# UiBoard.net
KiCad netlist of a schematic drawn in Altium Designer
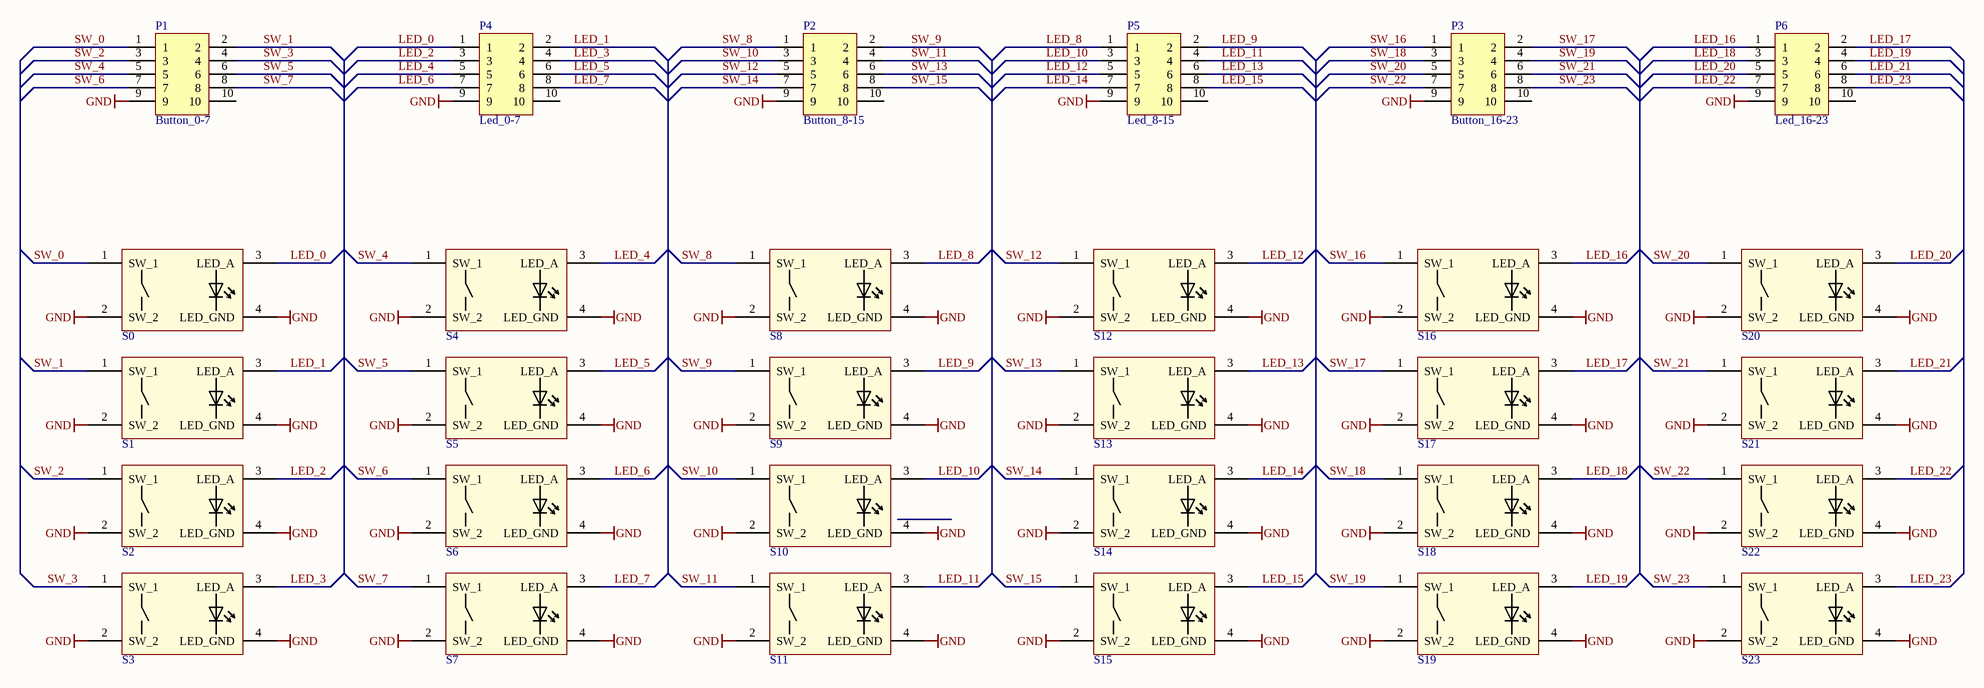
[diagram p0: UiBoard.SchDoc]

(export (version "E")
  (design (tool "Eeschema 10.0.6"))
  (components
    (comp (ref "P1")
      (value "Button_0-7")
      (footprint "10pol Header tilted:10 pol Header tilted")
      (description "10 pol Header")
      (fields (field (name "PUBLISHER") "NONLINEAR LABS"))
      (libsource (lib "10polHeader") (part "10 pol Header"))
    )
    (comp (ref "P2")
      (value "Button_8-15")
      (footprint "10pol Header tilted:10 pol Header tilted")
      (description "10 pol Header")
      (fields (field (name "PUBLISHER") "NONLINEAR LABS"))
      (libsource (lib "10polHeader") (part "10 pol Header"))
    )
    (comp (ref "P3")
      (value "Button_16-23")
      (footprint "10pol Header tilted:10 pol Header tilted")
      (description "10 pol Header")
      (fields (field (name "PUBLISHER") "NONLINEAR LABS"))
      (libsource (lib "10polHeader") (part "10 pol Header"))
    )
    (comp (ref "P4")
      (value "Led_0-7")
      (footprint "10pol Header tilted:10 pol Header tilted")
      (description "10 pol Header")
      (fields (field (name "PUBLISHER") "NONLINEAR LABS"))
      (libsource (lib "10polHeader") (part "10 pol Header"))
    )
    (comp (ref "P5")
      (value "Led_8-15")
      (footprint "10pol Header tilted:10 pol Header tilted")
      (description "10 pol Header")
      (fields (field (name "PUBLISHER") "NONLINEAR LABS"))
      (libsource (lib "10polHeader") (part "10 pol Header"))
    )
    (comp (ref "P6")
      (value "Led_16-23")
      (footprint "10pol Header tilted:10 pol Header tilted")
      (description "10 pol Header")
      (fields (field (name "PUBLISHER") "NONLINEAR LABS"))
      (libsource (lib "10polHeader") (part "10 pol Header"))
    )
    (comp (ref "S0")
      (value "Switch + LED")
      (footprint "Marquardt Taster 6425")
      (description "Marquardt Key Switch with LED - Type 6425")
      (fields (field (name "PUBLISHER") "Altium Limited"))
      (libsource (lib "SwitchLed") (part "Switch + LED"))
    )
    (comp (ref "S1")
      (value "Switch + LED")
      (footprint "Marquardt Taster 6425")
      (description "Marquardt Key Switch with LED - Type 6425")
      (fields (field (name "PUBLISHER") "Altium Limited"))
      (libsource (lib "SwitchLed") (part "Switch + LED"))
    )
    (comp (ref "S2")
      (value "Switch + LED")
      (footprint "Marquardt Taster 6425")
      (description "Marquardt Key Switch with LED - Type 6425")
      (fields (field (name "PUBLISHER") "Altium Limited"))
      (libsource (lib "SwitchLed") (part "Switch + LED"))
    )
    (comp (ref "S3")
      (value "Switch + LED")
      (footprint "Marquardt Taster 6425")
      (description "Marquardt Key Switch with LED - Type 6425")
      (fields (field (name "PUBLISHER") "Altium Limited"))
      (libsource (lib "SwitchLed") (part "Switch + LED"))
    )
    (comp (ref "S4")
      (value "Switch + LED")
      (footprint "Marquardt Taster 6425")
      (description "Marquardt Key Switch with LED - Type 6425")
      (fields (field (name "PUBLISHER") "Altium Limited"))
      (libsource (lib "SwitchLed") (part "Switch + LED"))
    )
    (comp (ref "S5")
      (value "Switch + LED")
      (footprint "Marquardt Taster 6425")
      (description "Marquardt Key Switch with LED - Type 6425")
      (fields (field (name "PUBLISHER") "Altium Limited"))
      (libsource (lib "SwitchLed") (part "Switch + LED"))
    )
    (comp (ref "S6")
      (value "Switch + LED")
      (footprint "Marquardt Taster 6425")
      (description "Marquardt Key Switch with LED - Type 6425")
      (fields (field (name "PUBLISHER") "Altium Limited"))
      (libsource (lib "SwitchLed") (part "Switch + LED"))
    )
    (comp (ref "S7")
      (value "Switch + LED")
      (footprint "Marquardt Taster 6425")
      (description "Marquardt Key Switch with LED - Type 6425")
      (fields (field (name "PUBLISHER") "Altium Limited"))
      (libsource (lib "SwitchLed") (part "Switch + LED"))
    )
    (comp (ref "S8")
      (value "Switch + LED")
      (footprint "Marquardt Taster 6425")
      (description "Marquardt Key Switch with LED - Type 6425")
      (fields (field (name "PUBLISHER") "Altium Limited"))
      (libsource (lib "SwitchLed") (part "Switch + LED"))
    )
    (comp (ref "S9")
      (value "Switch + LED")
      (footprint "Marquardt Taster 6425")
      (description "Marquardt Key Switch with LED - Type 6425")
      (fields (field (name "PUBLISHER") "Altium Limited"))
      (libsource (lib "SwitchLed") (part "Switch + LED"))
    )
    (comp (ref "S10")
      (value "Switch + LED")
      (footprint "Marquardt Taster 6425")
      (description "Marquardt Key Switch with LED - Type 6425")
      (fields (field (name "PUBLISHER") "Altium Limited"))
      (libsource (lib "SwitchLed") (part "Switch + LED"))
    )
    (comp (ref "S11")
      (value "Switch + LED")
      (footprint "Marquardt Taster 6425")
      (description "Marquardt Key Switch with LED - Type 6425")
      (fields (field (name "PUBLISHER") "Altium Limited"))
      (libsource (lib "SwitchLed") (part "Switch + LED"))
    )
    (comp (ref "S12")
      (value "Switch + LED")
      (footprint "Marquardt Taster 6425")
      (description "Marquardt Key Switch with LED - Type 6425")
      (fields (field (name "PUBLISHER") "Altium Limited"))
      (libsource (lib "SwitchLed") (part "Switch + LED"))
    )
    (comp (ref "S13")
      (value "Switch + LED")
      (footprint "Marquardt Taster 6425")
      (description "Marquardt Key Switch with LED - Type 6425")
      (fields (field (name "PUBLISHER") "Altium Limited"))
      (libsource (lib "SwitchLed") (part "Switch + LED"))
    )
    (comp (ref "S14")
      (value "Switch + LED")
      (footprint "Marquardt Taster 6425")
      (description "Marquardt Key Switch with LED - Type 6425")
      (fields (field (name "PUBLISHER") "Altium Limited"))
      (libsource (lib "SwitchLed") (part "Switch + LED"))
    )
    (comp (ref "S15")
      (value "Switch + LED")
      (footprint "Marquardt Taster 6425")
      (description "Marquardt Key Switch with LED - Type 6425")
      (fields (field (name "PUBLISHER") "Altium Limited"))
      (libsource (lib "SwitchLed") (part "Switch + LED"))
    )
    (comp (ref "S16")
      (value "Switch + LED")
      (footprint "Marquardt Taster 6425")
      (description "Marquardt Key Switch with LED - Type 6425")
      (fields (field (name "PUBLISHER") "Altium Limited"))
      (libsource (lib "SwitchLed") (part "Switch + LED"))
    )
    (comp (ref "S17")
      (value "Switch + LED")
      (footprint "Marquardt Taster 6425")
      (description "Marquardt Key Switch with LED - Type 6425")
      (fields (field (name "PUBLISHER") "Altium Limited"))
      (libsource (lib "SwitchLed") (part "Switch + LED"))
    )
    (comp (ref "S18")
      (value "Switch + LED")
      (footprint "Marquardt Taster 6425")
      (description "Marquardt Key Switch with LED - Type 6425")
      (fields (field (name "PUBLISHER") "Altium Limited"))
      (libsource (lib "SwitchLed") (part "Switch + LED"))
    )
    (comp (ref "S19")
      (value "Switch + LED")
      (footprint "Marquardt Taster 6425")
      (description "Marquardt Key Switch with LED - Type 6425")
      (fields (field (name "PUBLISHER") "Altium Limited"))
      (libsource (lib "SwitchLed") (part "Switch + LED"))
    )
    (comp (ref "S20")
      (value "Switch + LED")
      (footprint "Marquardt Taster 6425")
      (description "Marquardt Key Switch with LED - Type 6425")
      (fields (field (name "PUBLISHER") "Altium Limited"))
      (libsource (lib "SwitchLed") (part "Switch + LED"))
    )
    (comp (ref "S21")
      (value "Switch + LED")
      (footprint "Marquardt Taster 6425")
      (description "Marquardt Key Switch with LED - Type 6425")
      (fields (field (name "PUBLISHER") "Altium Limited"))
      (libsource (lib "SwitchLed") (part "Switch + LED"))
    )
    (comp (ref "S22")
      (value "Switch + LED")
      (footprint "Marquardt Taster 6425")
      (description "Marquardt Key Switch with LED - Type 6425")
      (fields (field (name "PUBLISHER") "Altium Limited"))
      (libsource (lib "SwitchLed") (part "Switch + LED"))
    )
    (comp (ref "S23")
      (value "Switch + LED")
      (footprint "Marquardt Taster 6425")
      (description "Marquardt Key Switch with LED - Type 6425")
      (fields (field (name "PUBLISHER") "Altium Limited"))
      (libsource (lib "SwitchLed") (part "Switch + LED"))
    )
  )
  (nets
    (net (code "1") (name "/LED_0") (class "Default")
      (node (ref "P4") (pin "1") (pinfunction "1_1") (pintype "passive"))
      (node (ref "S0") (pin "3") (pinfunction "LED_A_3") (pintype "passive"))
    )
    (net (code "2") (name "/LED_1") (class "Default")
      (node (ref "P4") (pin "2") (pinfunction "2_2") (pintype "passive"))
      (node (ref "S1") (pin "3") (pinfunction "LED_A_3") (pintype "passive"))
    )
    (net (code "3") (name "/LED_2") (class "Default")
      (node (ref "P4") (pin "3") (pinfunction "3_3") (pintype "passive"))
      (node (ref "S2") (pin "3") (pinfunction "LED_A_3") (pintype "passive"))
    )
    (net (code "4") (name "/LED_3") (class "Default")
      (node (ref "P4") (pin "4") (pinfunction "4_4") (pintype "passive"))
      (node (ref "S3") (pin "3") (pinfunction "LED_A_3") (pintype "passive"))
    )
    (net (code "5") (name "/LED_4") (class "Default")
      (node (ref "P4") (pin "5") (pinfunction "5_5") (pintype "passive"))
      (node (ref "S4") (pin "3") (pinfunction "LED_A_3") (pintype "passive"))
    )
    (net (code "6") (name "/LED_5") (class "Default")
      (node (ref "P4") (pin "6") (pinfunction "6_6") (pintype "passive"))
      (node (ref "S5") (pin "3") (pinfunction "LED_A_3") (pintype "passive"))
    )
    (net (code "7") (name "/LED_6") (class "Default")
      (node (ref "P4") (pin "7") (pinfunction "7_7") (pintype "passive"))
      (node (ref "S6") (pin "3") (pinfunction "LED_A_3") (pintype "passive"))
    )
    (net (code "8") (name "/LED_7") (class "Default")
      (node (ref "P4") (pin "8") (pinfunction "8_8") (pintype "passive"))
      (node (ref "S7") (pin "3") (pinfunction "LED_A_3") (pintype "passive"))
    )
    (net (code "9") (name "/LED_8") (class "Default")
      (node (ref "P5") (pin "1") (pinfunction "1_1") (pintype "passive"))
      (node (ref "S8") (pin "3") (pinfunction "LED_A_3") (pintype "passive"))
    )
    (net (code "10") (name "/LED_9") (class "Default")
      (node (ref "P5") (pin "2") (pinfunction "2_2") (pintype "passive"))
      (node (ref "S9") (pin "3") (pinfunction "LED_A_3") (pintype "passive"))
    )
    (net (code "11") (name "/LED_10") (class "Default")
      (node (ref "P5") (pin "3") (pinfunction "3_3") (pintype "passive"))
      (node (ref "S10") (pin "3") (pinfunction "LED_A_3") (pintype "passive"))
    )
    (net (code "12") (name "/LED_11") (class "Default")
      (node (ref "P5") (pin "4") (pinfunction "4_4") (pintype "passive"))
      (node (ref "S11") (pin "3") (pinfunction "LED_A_3") (pintype "passive"))
    )
    (net (code "13") (name "/LED_12") (class "Default")
      (node (ref "P5") (pin "5") (pinfunction "5_5") (pintype "passive"))
      (node (ref "S12") (pin "3") (pinfunction "LED_A_3") (pintype "passive"))
    )
    (net (code "14") (name "/LED_13") (class "Default")
      (node (ref "P5") (pin "6") (pinfunction "6_6") (pintype "passive"))
      (node (ref "S13") (pin "3") (pinfunction "LED_A_3") (pintype "passive"))
    )
    (net (code "15") (name "/LED_14") (class "Default")
      (node (ref "P5") (pin "7") (pinfunction "7_7") (pintype "passive"))
      (node (ref "S14") (pin "3") (pinfunction "LED_A_3") (pintype "passive"))
    )
    (net (code "16") (name "/LED_15") (class "Default")
      (node (ref "P5") (pin "8") (pinfunction "8_8") (pintype "passive"))
      (node (ref "S15") (pin "3") (pinfunction "LED_A_3") (pintype "passive"))
    )
    (net (code "17") (name "/LED_16") (class "Default")
      (node (ref "P6") (pin "1") (pinfunction "1_1") (pintype "passive"))
      (node (ref "S16") (pin "3") (pinfunction "LED_A_3") (pintype "passive"))
    )
    (net (code "18") (name "/LED_17") (class "Default")
      (node (ref "P6") (pin "2") (pinfunction "2_2") (pintype "passive"))
      (node (ref "S17") (pin "3") (pinfunction "LED_A_3") (pintype "passive"))
    )
    (net (code "19") (name "/LED_18") (class "Default")
      (node (ref "P6") (pin "3") (pinfunction "3_3") (pintype "passive"))
      (node (ref "S18") (pin "3") (pinfunction "LED_A_3") (pintype "passive"))
    )
    (net (code "20") (name "/LED_19") (class "Default")
      (node (ref "P6") (pin "4") (pinfunction "4_4") (pintype "passive"))
      (node (ref "S19") (pin "3") (pinfunction "LED_A_3") (pintype "passive"))
    )
    (net (code "21") (name "/LED_20") (class "Default")
      (node (ref "P6") (pin "5") (pinfunction "5_5") (pintype "passive"))
      (node (ref "S20") (pin "3") (pinfunction "LED_A_3") (pintype "passive"))
    )
    (net (code "22") (name "/LED_21") (class "Default")
      (node (ref "P6") (pin "6") (pinfunction "6_6") (pintype "passive"))
      (node (ref "S21") (pin "3") (pinfunction "LED_A_3") (pintype "passive"))
    )
    (net (code "23") (name "/LED_22") (class "Default")
      (node (ref "P6") (pin "7") (pinfunction "7_7") (pintype "passive"))
      (node (ref "S22") (pin "3") (pinfunction "LED_A_3") (pintype "passive"))
    )
    (net (code "24") (name "/LED_23") (class "Default")
      (node (ref "P6") (pin "8") (pinfunction "8_8") (pintype "passive"))
      (node (ref "S23") (pin "3") (pinfunction "LED_A_3") (pintype "passive"))
    )
    (net (code "25") (name "/SW_0") (class "Default")
      (node (ref "P1") (pin "1") (pinfunction "1_1") (pintype "passive"))
      (node (ref "S0") (pin "1") (pinfunction "SW_1_1") (pintype "passive"))
    )
    (net (code "26") (name "/SW_1") (class "Default")
      (node (ref "P1") (pin "2") (pinfunction "2_2") (pintype "passive"))
      (node (ref "S1") (pin "1") (pinfunction "SW_1_1") (pintype "passive"))
    )
    (net (code "27") (name "/SW_2") (class "Default")
      (node (ref "P1") (pin "3") (pinfunction "3_3") (pintype "passive"))
      (node (ref "S2") (pin "1") (pinfunction "SW_1_1") (pintype "passive"))
    )
    (net (code "28") (name "/SW_3") (class "Default")
      (node (ref "P1") (pin "4") (pinfunction "4_4") (pintype "passive"))
      (node (ref "S3") (pin "1") (pinfunction "SW_1_1") (pintype "passive"))
    )
    (net (code "29") (name "/SW_4") (class "Default")
      (node (ref "P1") (pin "5") (pinfunction "5_5") (pintype "passive"))
      (node (ref "S4") (pin "1") (pinfunction "SW_1_1") (pintype "passive"))
    )
    (net (code "30") (name "/SW_5") (class "Default")
      (node (ref "P1") (pin "6") (pinfunction "6_6") (pintype "passive"))
      (node (ref "S5") (pin "1") (pinfunction "SW_1_1") (pintype "passive"))
    )
    (net (code "31") (name "/SW_6") (class "Default")
      (node (ref "P1") (pin "7") (pinfunction "7_7") (pintype "passive"))
      (node (ref "S6") (pin "1") (pinfunction "SW_1_1") (pintype "passive"))
    )
    (net (code "32") (name "/SW_7") (class "Default")
      (node (ref "P1") (pin "8") (pinfunction "8_8") (pintype "passive"))
      (node (ref "S7") (pin "1") (pinfunction "SW_1_1") (pintype "passive"))
    )
    (net (code "33") (name "/SW_8") (class "Default")
      (node (ref "P2") (pin "1") (pinfunction "1_1") (pintype "passive"))
      (node (ref "S8") (pin "1") (pinfunction "SW_1_1") (pintype "passive"))
    )
    (net (code "34") (name "/SW_9") (class "Default")
      (node (ref "P2") (pin "2") (pinfunction "2_2") (pintype "passive"))
      (node (ref "S9") (pin "1") (pinfunction "SW_1_1") (pintype "passive"))
    )
    (net (code "35") (name "/SW_10") (class "Default")
      (node (ref "P2") (pin "3") (pinfunction "3_3") (pintype "passive"))
      (node (ref "S10") (pin "1") (pinfunction "SW_1_1") (pintype "passive"))
    )
    (net (code "36") (name "/SW_11") (class "Default")
      (node (ref "P2") (pin "4") (pinfunction "4_4") (pintype "passive"))
      (node (ref "S11") (pin "1") (pinfunction "SW_1_1") (pintype "passive"))
    )
    (net (code "37") (name "/SW_12") (class "Default")
      (node (ref "P2") (pin "5") (pinfunction "5_5") (pintype "passive"))
      (node (ref "S12") (pin "1") (pinfunction "SW_1_1") (pintype "passive"))
    )
    (net (code "38") (name "/SW_13") (class "Default")
      (node (ref "P2") (pin "6") (pinfunction "6_6") (pintype "passive"))
      (node (ref "S13") (pin "1") (pinfunction "SW_1_1") (pintype "passive"))
    )
    (net (code "39") (name "/SW_14") (class "Default")
      (node (ref "P2") (pin "7") (pinfunction "7_7") (pintype "passive"))
      (node (ref "S14") (pin "1") (pinfunction "SW_1_1") (pintype "passive"))
    )
    (net (code "40") (name "/SW_15") (class "Default")
      (node (ref "P2") (pin "8") (pinfunction "8_8") (pintype "passive"))
      (node (ref "S15") (pin "1") (pinfunction "SW_1_1") (pintype "passive"))
    )
    (net (code "41") (name "/SW_16") (class "Default")
      (node (ref "P3") (pin "1") (pinfunction "1_1") (pintype "passive"))
      (node (ref "S16") (pin "1") (pinfunction "SW_1_1") (pintype "passive"))
    )
    (net (code "42") (name "/SW_17") (class "Default")
      (node (ref "P3") (pin "2") (pinfunction "2_2") (pintype "passive"))
      (node (ref "S17") (pin "1") (pinfunction "SW_1_1") (pintype "passive"))
    )
    (net (code "43") (name "/SW_18") (class "Default")
      (node (ref "P3") (pin "3") (pinfunction "3_3") (pintype "passive"))
      (node (ref "S18") (pin "1") (pinfunction "SW_1_1") (pintype "passive"))
    )
    (net (code "44") (name "/SW_19") (class "Default")
      (node (ref "P3") (pin "4") (pinfunction "4_4") (pintype "passive"))
      (node (ref "S19") (pin "1") (pinfunction "SW_1_1") (pintype "passive"))
    )
    (net (code "45") (name "/SW_20") (class "Default")
      (node (ref "P3") (pin "5") (pinfunction "5_5") (pintype "passive"))
      (node (ref "S20") (pin "1") (pinfunction "SW_1_1") (pintype "passive"))
    )
    (net (code "46") (name "/SW_21") (class "Default")
      (node (ref "P3") (pin "6") (pinfunction "6_6") (pintype "passive"))
      (node (ref "S21") (pin "1") (pinfunction "SW_1_1") (pintype "passive"))
    )
    (net (code "47") (name "/SW_22") (class "Default")
      (node (ref "P3") (pin "7") (pinfunction "7_7") (pintype "passive"))
      (node (ref "S22") (pin "1") (pinfunction "SW_1_1") (pintype "passive"))
    )
    (net (code "48") (name "/SW_23") (class "Default")
      (node (ref "P3") (pin "8") (pinfunction "8_8") (pintype "passive"))
      (node (ref "S23") (pin "1") (pinfunction "SW_1_1") (pintype "passive"))
    )
    (net (code "49") (name "GND") (class "Default")
      (node (ref "P1") (pin "9") (pinfunction "9_9") (pintype "passive"))
      (node (ref "P2") (pin "9") (pinfunction "9_9") (pintype "passive"))
      (node (ref "P3") (pin "9") (pinfunction "9_9") (pintype "passive"))
      (node (ref "P4") (pin "9") (pinfunction "9_9") (pintype "passive"))
      (node (ref "P5") (pin "9") (pinfunction "9_9") (pintype "passive"))
      (node (ref "P6") (pin "9") (pinfunction "9_9") (pintype "passive"))
      (node (ref "S0") (pin "2") (pinfunction "SW_2_2") (pintype "passive"))
      (node (ref "S0") (pin "4") (pinfunction "LED_GND_4") (pintype "passive"))
      (node (ref "S1") (pin "2") (pinfunction "SW_2_2") (pintype "passive"))
      (node (ref "S1") (pin "4") (pinfunction "LED_GND_4") (pintype "passive"))
      (node (ref "S10") (pin "2") (pinfunction "SW_2_2") (pintype "passive"))
      (node (ref "S10") (pin "4") (pinfunction "LED_GND_4") (pintype "passive"))
      (node (ref "S11") (pin "2") (pinfunction "SW_2_2") (pintype "passive"))
      (node (ref "S11") (pin "4") (pinfunction "LED_GND_4") (pintype "passive"))
      (node (ref "S12") (pin "2") (pinfunction "SW_2_2") (pintype "passive"))
      (node (ref "S12") (pin "4") (pinfunction "LED_GND_4") (pintype "passive"))
      (node (ref "S13") (pin "2") (pinfunction "SW_2_2") (pintype "passive"))
      (node (ref "S13") (pin "4") (pinfunction "LED_GND_4") (pintype "passive"))
      (node (ref "S14") (pin "2") (pinfunction "SW_2_2") (pintype "passive"))
      (node (ref "S14") (pin "4") (pinfunction "LED_GND_4") (pintype "passive"))
      (node (ref "S15") (pin "2") (pinfunction "SW_2_2") (pintype "passive"))
      (node (ref "S15") (pin "4") (pinfunction "LED_GND_4") (pintype "passive"))
      (node (ref "S16") (pin "2") (pinfunction "SW_2_2") (pintype "passive"))
      (node (ref "S16") (pin "4") (pinfunction "LED_GND_4") (pintype "passive"))
      (node (ref "S17") (pin "2") (pinfunction "SW_2_2") (pintype "passive"))
      (node (ref "S17") (pin "4") (pinfunction "LED_GND_4") (pintype "passive"))
      (node (ref "S18") (pin "2") (pinfunction "SW_2_2") (pintype "passive"))
      (node (ref "S18") (pin "4") (pinfunction "LED_GND_4") (pintype "passive"))
      (node (ref "S19") (pin "2") (pinfunction "SW_2_2") (pintype "passive"))
      (node (ref "S19") (pin "4") (pinfunction "LED_GND_4") (pintype "passive"))
      (node (ref "S2") (pin "2") (pinfunction "SW_2_2") (pintype "passive"))
      (node (ref "S2") (pin "4") (pinfunction "LED_GND_4") (pintype "passive"))
      (node (ref "S20") (pin "2") (pinfunction "SW_2_2") (pintype "passive"))
      (node (ref "S20") (pin "4") (pinfunction "LED_GND_4") (pintype "passive"))
      (node (ref "S21") (pin "2") (pinfunction "SW_2_2") (pintype "passive"))
      (node (ref "S21") (pin "4") (pinfunction "LED_GND_4") (pintype "passive"))
      (node (ref "S22") (pin "2") (pinfunction "SW_2_2") (pintype "passive"))
      (node (ref "S22") (pin "4") (pinfunction "LED_GND_4") (pintype "passive"))
      (node (ref "S23") (pin "2") (pinfunction "SW_2_2") (pintype "passive"))
      (node (ref "S23") (pin "4") (pinfunction "LED_GND_4") (pintype "passive"))
      (node (ref "S3") (pin "2") (pinfunction "SW_2_2") (pintype "passive"))
      (node (ref "S3") (pin "4") (pinfunction "LED_GND_4") (pintype "passive"))
      (node (ref "S4") (pin "2") (pinfunction "SW_2_2") (pintype "passive"))
      (node (ref "S4") (pin "4") (pinfunction "LED_GND_4") (pintype "passive"))
      (node (ref "S5") (pin "2") (pinfunction "SW_2_2") (pintype "passive"))
      (node (ref "S5") (pin "4") (pinfunction "LED_GND_4") (pintype "passive"))
      (node (ref "S6") (pin "2") (pinfunction "SW_2_2") (pintype "passive"))
      (node (ref "S6") (pin "4") (pinfunction "LED_GND_4") (pintype "passive"))
      (node (ref "S7") (pin "2") (pinfunction "SW_2_2") (pintype "passive"))
      (node (ref "S7") (pin "4") (pinfunction "LED_GND_4") (pintype "passive"))
      (node (ref "S8") (pin "2") (pinfunction "SW_2_2") (pintype "passive"))
      (node (ref "S8") (pin "4") (pinfunction "LED_GND_4") (pintype "passive"))
      (node (ref "S9") (pin "2") (pinfunction "SW_2_2") (pintype "passive"))
      (node (ref "S9") (pin "4") (pinfunction "LED_GND_4") (pintype "passive"))
    )
    (net (code "50") (name "unconnected-(P1-Pad10)") (class "Default")
      (node (ref "P1") (pin "10") (pinfunction "10_10") (pintype "passive"))
    )
    (net (code "51") (name "unconnected-(P2-Pad10)") (class "Default")
      (node (ref "P2") (pin "10") (pinfunction "10_10") (pintype "passive"))
    )
    (net (code "52") (name "unconnected-(P3-Pad10)") (class "Default")
      (node (ref "P3") (pin "10") (pinfunction "10_10") (pintype "passive"))
    )
    (net (code "53") (name "unconnected-(P4-Pad10)") (class "Default")
      (node (ref "P4") (pin "10") (pinfunction "10_10") (pintype "passive"))
    )
    (net (code "54") (name "unconnected-(P5-Pad10)") (class "Default")
      (node (ref "P5") (pin "10") (pinfunction "10_10") (pintype "passive"))
    )
    (net (code "55") (name "unconnected-(P6-Pad10)") (class "Default")
      (node (ref "P6") (pin "10") (pinfunction "10_10") (pintype "passive"))
    )
  )
)
